# AWSAM5_CS704.net
KiCad netlist of a schematic drawn in Altium Designer
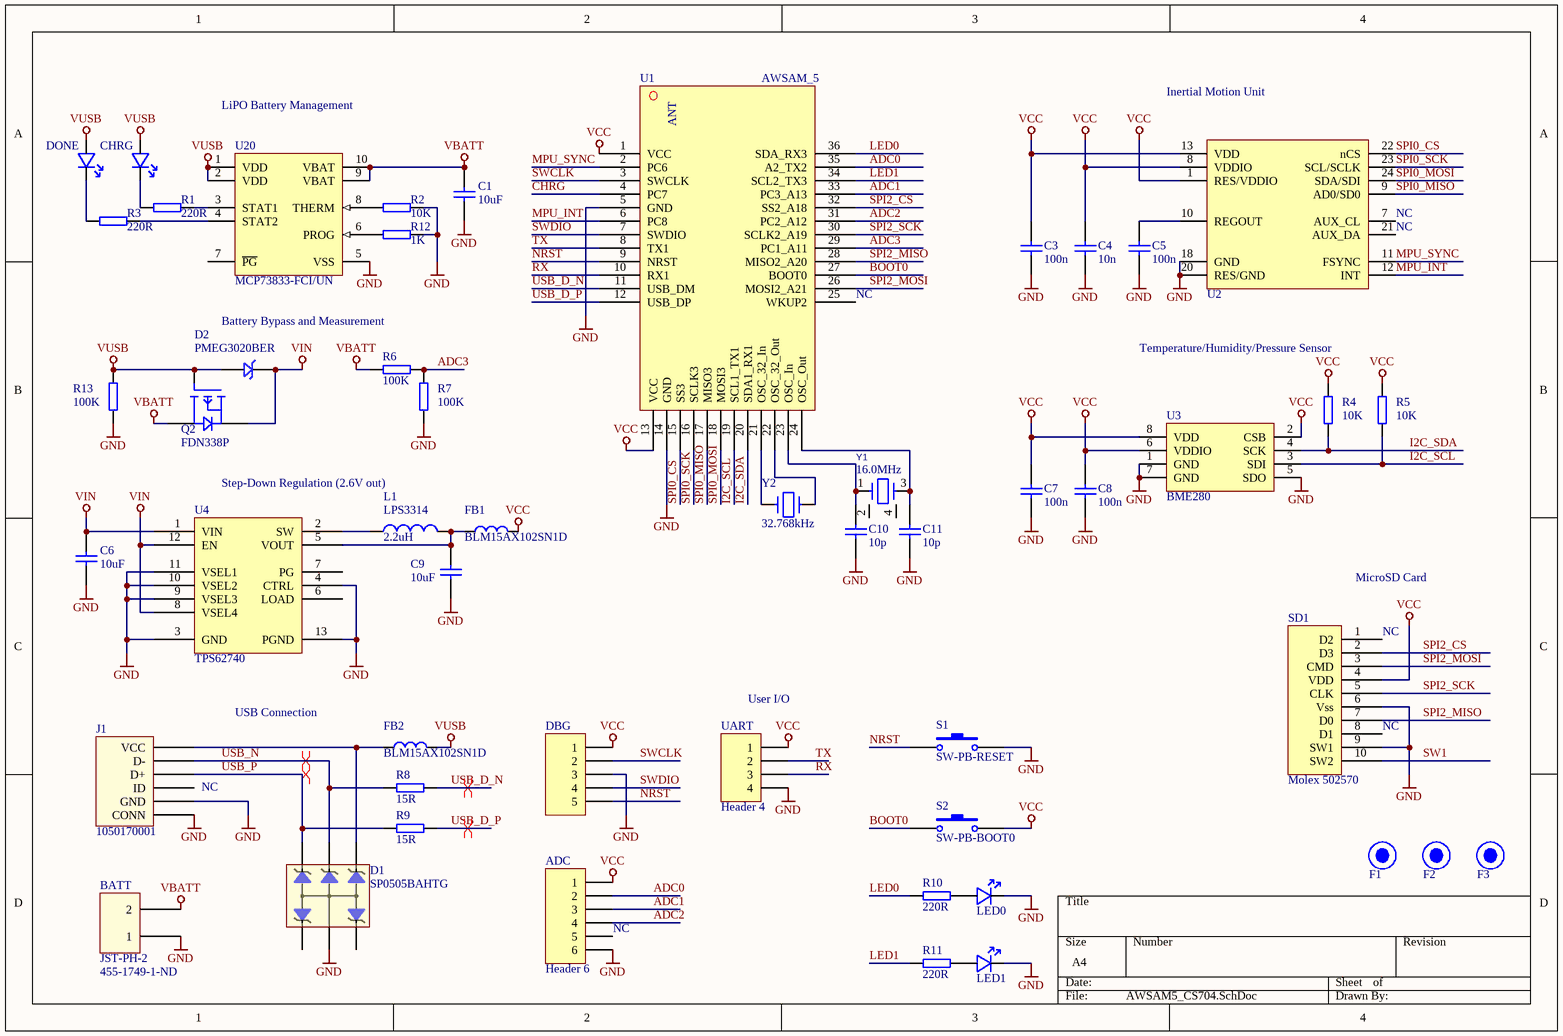
[diagram p0: AWSAM5_CS704.SchDoc]

(export (version "E")
  (design (tool "Eeschema 10.0.6"))
  (components
    (comp (ref "ADC")
      (value "Header 6")
      (footprint "HDR1X6")
      (description "Header, 6-Pin")
      (fields (field (name "PUBLISHER") "Altium Limited"))
      (libsource (lib "Miscellaneous Connectors") (part "Header 6"))
    )
    (comp (ref "BATT")
      (value "JST-PH-2")
      (footprint "JST-PH-2POS")
      (description "CONN SM JST PH 2-POS")
      (fields (field (name "SUPPLIER PART NUMBER 1") "455-1749-1-ND"))
      (libsource (lib "electronpowered") (part "S2B-PH-SM4-TB"))
    )
    (comp (ref "C1")
      (value "10uF")
      (footprint "CAP0603")
      (description "CAP SM 0603 X5R 10uF")
      (fields (field (name "PART NUMBER") "CAP-SM-0603-X5R-10uF") (field (name "MANUFACTURER") "GENERIC"))
      (libsource (lib "electronpowered") (part "CAP"))
    )
    (comp (ref "C3")
      (value "100n")
      (footprint "CAP0402")
      (description "CAP SM 0402 X7R 100NF")
      (fields (field (name "PART NUMBER") "CAP-SM-0402-X7R-100NF") (field (name "MANUFACTURER") "GENERIC"))
      (libsource (lib "electronpowered") (part "CAP"))
    )
    (comp (ref "C4")
      (value "10n")
      (footprint "CAP0402")
      (description "CAP SM 0402 X7R 10NF")
      (fields (field (name "PART NUMBER") "CAP-SM-0402-X7R-10NF") (field (name "MANUFACTURER") "GENERIC"))
      (libsource (lib "electronpowered") (part "CAP"))
    )
    (comp (ref "C5")
      (value "100n")
      (footprint "CAP0402")
      (description "CAP SM 0402 X7R 100NF")
      (fields (field (name "PART NUMBER") "CAP-SM-0402-X7R-100NF") (field (name "MANUFACTURER") "GENERIC"))
      (libsource (lib "electronpowered") (part "CAP"))
    )
    (comp (ref "C6")
      (value "10uF")
      (footprint "CAP0603")
      (description "CAP SM 0603 X5R 10uF")
      (fields (field (name "PART NUMBER") "CAP-SM-0603-X5R-10uF") (field (name "MANUFACTURER") "GENERIC"))
      (libsource (lib "electronpowered") (part "CAP"))
    )
    (comp (ref "C7")
      (value "100n")
      (footprint "CAP0402")
      (description "CAP SM 0402 X7R 100NF")
      (fields (field (name "PART NUMBER") "CAP-SM-0402-X7R-100NF") (field (name "MANUFACTURER") "GENERIC"))
      (libsource (lib "electronpowered") (part "CAP"))
    )
    (comp (ref "C8")
      (value "100n")
      (footprint "CAP0402")
      (description "CAP SM 0402 X7R 100NF")
      (fields (field (name "PART NUMBER") "CAP-SM-0402-X7R-100NF") (field (name "MANUFACTURER") "GENERIC"))
      (libsource (lib "electronpowered") (part "CAP"))
    )
    (comp (ref "C9")
      (value "10uF")
      (footprint "CAP0603")
      (description "CAP SM 0603 X5R 10uF")
      (fields (field (name "PART NUMBER") "CAP-SM-0603-X5R-10uF") (field (name "MANUFACTURER") "GENERIC"))
      (libsource (lib "electronpowered") (part "CAP"))
    )
    (comp (ref "C10")
      (value "10p")
      (footprint "CAP0402")
      (description "CAP SM 0402 NP0 10PF")
      (fields (field (name "PART NUMBER") "CAP-SM-0402-NP0-10PF") (field (name "MANUFACTURER") "GENERIC"))
      (libsource (lib "electronpowered") (part "CAP"))
    )
    (comp (ref "C11")
      (value "10p")
      (footprint "CAP0402")
      (description "CAP SM 0402 NP0 10PF")
      (fields (field (name "PART NUMBER") "CAP-SM-0402-NP0-10PF") (field (name "MANUFACTURER") "GENERIC"))
      (libsource (lib "electronpowered") (part "CAP"))
    )
    (comp (ref "CHRG")
      (value "LED")
      (footprint "LED0603P")
      (description "LED 0603 RED")
      (fields (field (name "PART NUMBER") "LED-0603-RED") (field (name "MANUFACTURER") "GENERIC"))
      (libsource (lib "electronpowered") (part "LED"))
    )
    (comp (ref "D1")
      (value "SP0505BAHTG")
      (footprint "SOT26A-6L")
      (description "IC DIODE TRANS VOLT SUPPR 5 PACKAGE")
      (fields (field (name "MANUFACTURER") "Little Fuse"))
      (libsource (lib "electronpowered") (part "SP0505BAHTG"))
    )
    (comp (ref "D2")
      (value "DIODE-SCHOTTKY")
      (footprint "SODFL350X110-2N")
      (description "DIODE  SCHOTTKY 1A 40V")
      (fields (field (name "PART NUMBER") "PMEG3020BER") (field (name "MANUFACTURER") "Panasonic"))
      (libsource (lib "electronpowered") (part "DIODE-SCHOTTKY"))
    )
    (comp (ref "DBG")
      (value "~")
      (footprint "HDR1X5")
      (description "Header, 5-Pin")
      (fields (field (name "PUBLISHER") "Altium Limited"))
      (libsource (lib "Miscellaneous Connectors") (part "Header 5"))
    )
    (comp (ref "DONE")
      (value "LED")
      (footprint "LED0603P")
      (description "LED 0603 RED")
      (fields (field (name "PART NUMBER") "LED-0603-RED") (field (name "MANUFACTURER") "GENERIC"))
      (libsource (lib "electronpowered") (part "LED"))
    )
    (comp (ref "F1")
      (value "FIDUCIAL")
      (footprint "FIDUCIAL-1MM")
      (description "FIDUCIAL 1MM CENTER")
      (fields (field (name "PART NUMBER") "FIDUCIAL-1MM"))
      (libsource (lib "electronpowered") (part "FIDUCIAL"))
    )
    (comp (ref "F2")
      (value "FIDUCIAL")
      (footprint "FIDUCIAL-1MM")
      (description "FIDUCIAL 1MM CENTER")
      (fields (field (name "PART NUMBER") "FIDUCIAL-1MM"))
      (libsource (lib "electronpowered") (part "FIDUCIAL"))
    )
    (comp (ref "F3")
      (value "FIDUCIAL")
      (footprint "FIDUCIAL-1MM")
      (description "FIDUCIAL 1MM CENTER")
      (fields (field (name "PART NUMBER") "FIDUCIAL-1MM"))
      (libsource (lib "electronpowered") (part "FIDUCIAL"))
    )
    (comp (ref "FB1")
      (value "IND")
      (footprint "IND0402")
      (description "FERRITE BEAD 350mA 0402")
      (fields (field (name "PART NUMBER") "BLM15AX102SN1D") (field (name "MANUFACTURER") "Murata"))
      (libsource (lib "electronpowered") (part "IND"))
    )
    (comp (ref "FB2")
      (value "IND")
      (footprint "IND0402")
      (description "FERRITE BEAD 350mA 0402")
      (fields (field (name "PART NUMBER") "BLM15AX102SN1D") (field (name "MANUFACTURER") "Murata"))
      (libsource (lib "electronpowered") (part "IND"))
    )
    (comp (ref "J1")
      (value "1050170001")
      (footprint "1050170001")
      (description "CONN RCPT MICRO USB R/A SMD")
      (fields (field (name "MANUFACTURER") "MOLEX"))
      (libsource (lib "electronpowered") (part "1050170001"))
    )
    (comp (ref "L1")
      (value "LPS3314")
      (footprint "CoilCraft- LPS3314")
      (description "Inductor")
      (fields (field (name "ALTIUM_VALUE") "2.2uH") (field (name "PUBLISHER") "Altium Limited"))
      (libsource (lib "Miscellaneous Devices") (part "Inductor"))
    )
    (comp (ref "LED0")
      (value "LED")
      (footprint "LED0603P")
      (description "LED 0603 RED")
      (fields (field (name "PART NUMBER") "LED-0603-RED") (field (name "MANUFACTURER") "GENERIC"))
      (libsource (lib "electronpowered") (part "LED"))
    )
    (comp (ref "LED1")
      (value "LED")
      (footprint "LED0603P")
      (description "LED 0603 RED")
      (fields (field (name "PART NUMBER") "LED-0603-RED") (field (name "MANUFACTURER") "GENERIC"))
      (libsource (lib "electronpowered") (part "LED"))
    )
    (comp (ref "Q2")
      (value "FET-PCH-DIODE")
      (footprint "SOT23-3")
      (description "MOSFET P-CH 20V 115MA SOT23-3")
      (fields (field (name "PART NUMBER") "FDN338P") (field (name "MANUFACTURER") "Fairchild"))
      (libsource (lib "electronpowered") (part "FET-PCH-DIODE"))
    )
    (comp (ref "R1")
      (value "220R")
      (footprint "SMT0402")
      (description "RES SM 0603 220R")
      (fields (field (name "Comment") "Resistor"))
      (libsource (lib "electronpowered") (part "RES-SM-0603-220R"))
    )
    (comp (ref "R2")
      (value "10K")
      (footprint "SMT0402")
      (description "RES SM 0402 10K")
      (fields (field (name "PART NUMBER") "RES-SM-0402-10K") (field (name "MANUFACTURER") "GENERIC"))
      (libsource (lib "electronpowered") (part "RES"))
    )
    (comp (ref "R3")
      (value "220R")
      (footprint "SMT0402")
      (description "RES SM 0603 220R")
      (fields (field (name "Comment") "Resistor"))
      (libsource (lib "electronpowered") (part "RES-SM-0603-220R"))
    )
    (comp (ref "R4")
      (value "10K")
      (footprint "SMT0402")
      (description "RES SM 0402 10K")
      (fields (field (name "PART NUMBER") "RES-SM-0402-10K") (field (name "MANUFACTURER") "GENERIC"))
      (libsource (lib "electronpowered") (part "RES"))
    )
    (comp (ref "R5")
      (value "10K")
      (footprint "SMT0402")
      (description "RES SM 0402 10K")
      (fields (field (name "PART NUMBER") "RES-SM-0402-10K") (field (name "MANUFACTURER") "GENERIC"))
      (libsource (lib "electronpowered") (part "RES"))
    )
    (comp (ref "R6")
      (value "100K")
      (footprint "SMT0402")
      (description "RES SM 0402 100K")
      (fields (field (name "PART NUMBER") "RES-SM-0402-100K") (field (name "MANUFACTURER") "GENERIC"))
      (libsource (lib "electronpowered") (part "RES"))
    )
    (comp (ref "R7")
      (value "100K")
      (footprint "SMT0402")
      (description "RES SM 0402 100K")
      (fields (field (name "PART NUMBER") "RES-SM-0402-100K") (field (name "MANUFACTURER") "GENERIC"))
      (libsource (lib "electronpowered") (part "RES"))
    )
    (comp (ref "R8")
      (value "15R")
      (footprint "SMT0402")
      (description "RES SM 0603 22K")
      (libsource (lib "electronpowered") (part "RES-SM-0603-22K"))
    )
    (comp (ref "R9")
      (value "15R")
      (footprint "SMT0402")
      (description "RES SM 0603 22K")
      (fields (field (name "Comment") "Resistor"))
      (libsource (lib "electronpowered") (part "RES-SM-0603-22K"))
    )
    (comp (ref "R10")
      (value "220R")
      (footprint "SMT0402")
      (description "RES SM 0603 220R")
      (fields (field (name "Comment") "Resistor"))
      (libsource (lib "electronpowered") (part "RES-SM-0603-220R"))
    )
    (comp (ref "R11")
      (value "220R")
      (footprint "SMT0402")
      (description "RES SM 0603 220R")
      (fields (field (name "Comment") "Resistor"))
      (libsource (lib "electronpowered") (part "RES-SM-0603-220R"))
    )
    (comp (ref "R12")
      (value "1K")
      (footprint "SMT0402")
      (description "RES SM 0402 1K")
      (fields (field (name "PART NUMBER") "RES-SM-0402-1K") (field (name "MANUFACTURER") "GENERIC"))
      (libsource (lib "electronpowered") (part "RES"))
    )
    (comp (ref "R13")
      (value "100K")
      (footprint "RES0402")
      (description "RES SM 0402 100K")
      (fields (field (name "PART NUMBER") "RES-SM-0402-100K") (field (name "MANUFACTURER") "GENERIC"))
      (libsource (lib "") (part "RES_1"))
    )
    (comp (ref "S1")
      (value "SW-PB-RESET")
      (footprint "MC32882 Switch")
      (description "Switch")
      (fields (field (name "PUBLISHER") "Altium Limited"))
      (libsource (lib "Miscellaneous Devices") (part "SW-PB"))
    )
    (comp (ref "S2")
      (value "SW-PB-BOOT0")
      (footprint "MC32882 Switch")
      (description "Switch")
      (fields (field (name "PUBLISHER") "Altium Limited"))
      (libsource (lib "Miscellaneous Devices") (part "SW-PB"))
    )
    (comp (ref "SD1")
      (value "Molex 502570")
      (footprint "micro SD")
      (description "CONN SM MICROSD")
      (libsource (lib "AWSAM_5") (part "MOLEX-502570"))
    )
    (comp (ref "U1") (value "AWSAM_5") (footprint "AWSAM_5") (libsource (lib "AWSAM_5") (part "AWSAM_5")))
    (comp (ref "U2")
      (value "MPU-9250")
      (footprint "QFN40P300X300X105_HS-25L")
      (description "IC 9DOF IMU")
      (fields (field (name "MANUFACTURER") "InvenSense"))
      (libsource (lib "electronpowered") (part "MPU-9250"))
    )
    (comp (ref "U3")
      (value "BME280")
      (footprint "BME280")
      (description "IC SENSOR PRESS/HUMID/TEMP")
      (fields (field (name "MANUFACTURER") "Bosch"))
      (libsource (lib "electronpowered") (part "BME280"))
    )
    (comp (ref "U4")
      (value "TPS62740")
      (footprint "TPS62740_12Pin")
      (description "IC REG BUCK")
      (fields (field (name "MANUFACTURER") "Texas Instruments"))
      (libsource (lib "electronpowered") (part "TPS62740"))
    )
    (comp (ref "U20")
      (value "MCP73833-FCI/UN")
      (footprint "MSOP-UN10_N")
      (fields (field (name "PUBLISHER") "Altium Limited"))
      (libsource (lib "Microchip Power Mgt Battery Management") (part "MCP73833-FCI/UN"))
    )
    (comp (ref "UART")
      (value "Header 4")
      (footprint "HDR1X4")
      (description "Header, 4-Pin")
      (fields (field (name "PUBLISHER") "Altium Limited"))
      (libsource (lib "Miscellaneous Connectors") (part "Header 4"))
    )
    (comp (ref "Y1")
      (value "16.0MHz")
      (footprint "AP7-00061")
      (description "16MHz uXtal, 3.2 x 2.5 mm SMD, CL=9pF, 15PPM, ESR=80ohm(Max.")
      (fields (field (name "TOLERANCE") "15ppm") (field (name "MANUFACTURER") "Epson Toyocom"))
      (libsource (lib "AltiumDbLib") (part "TSX-3225"))
    )
    (comp (ref "Y2")
      (value "CM315-32.768KEZF-UT")
      (footprint "SMD Crystal 32kHz")
      (description "CRYSTAL 32.768KHZ 12.5PF SMD")
      (fields (field (name "MANUFACTURER") "Citizen Finetech Miyota") (field (name "FREQUENCY") "32.768kHz"))
      (libsource (lib "AWSAM_5") (part "CM315-32.768KEZF-UT"))
    )
  )
  (nets
    (net (code "1") (name "/ADC0") (class "Default")
      (node (ref "ADC") (pin "2") (pinfunction "2_2") (pintype "passive"))
      (node (ref "U1") (pin "35") (pinfunction "A2_TX2_35") (pintype "passive"))
    )
    (net (code "2") (name "/ADC1") (class "Default")
      (node (ref "ADC") (pin "3") (pinfunction "3_3") (pintype "passive"))
      (node (ref "U1") (pin "33") (pinfunction "PC3_A13_33") (pintype "passive"))
    )
    (net (code "3") (name "/ADC2") (class "Default")
      (node (ref "ADC") (pin "4") (pinfunction "4_4") (pintype "passive"))
      (node (ref "U1") (pin "31") (pinfunction "PC2_A12_31") (pintype "passive"))
    )
    (net (code "4") (name "/ADC3") (class "Default")
      (node (ref "R6") (pin "1") (pinfunction "1_1") (pintype "passive"))
      (node (ref "R7") (pin "2") (pinfunction "2_2") (pintype "passive"))
      (node (ref "U1") (pin "29") (pinfunction "PC1_A11_29") (pintype "passive"))
    )
    (net (code "5") (name "/BOOT0") (class "Default")
      (node (ref "S2") (pin "1") (pinfunction "1_1") (pintype "passive"))
      (node (ref "U1") (pin "27") (pinfunction "BOOT0_27") (pintype "passive"))
    )
    (net (code "6") (name "/CHRG") (class "Default")
      (node (ref "U1") (pin "4") (pinfunction "PC7_4") (pintype "passive"))
    )
    (net (code "7") (name "/I2C_SCL") (class "Default")
      (node (ref "R5") (pin "1") (pinfunction "1_1") (pintype "passive"))
      (node (ref "U1") (pin "19") (pinfunction "SCL1_TX1_19") (pintype "passive"))
      (node (ref "U3") (pin "3") (pinfunction "SDI_3") (pintype "passive"))
    )
    (net (code "8") (name "/I2C_SDA") (class "Default")
      (node (ref "R4") (pin "1") (pinfunction "1_1") (pintype "passive"))
      (node (ref "U1") (pin "20") (pinfunction "SDA1_RX1_20") (pintype "passive"))
      (node (ref "U3") (pin "4") (pinfunction "SCK_4") (pintype "passive"))
    )
    (net (code "9") (name "/LED0") (class "Default")
      (node (ref "R10") (pin "2") (pinfunction "2_2") (pintype "passive"))
      (node (ref "U1") (pin "36") (pinfunction "SDA_RX3_36") (pintype "passive"))
    )
    (net (code "10") (name "/LED1") (class "Default")
      (node (ref "R11") (pin "2") (pinfunction "2_2") (pintype "passive"))
      (node (ref "U1") (pin "34") (pinfunction "SCL2_TX3_34") (pintype "passive"))
    )
    (net (code "11") (name "/MPU_INT") (class "Default")
      (node (ref "U1") (pin "6") (pinfunction "PC8_6") (pintype "passive"))
      (node (ref "U2") (pin "12") (pinfunction "INT_12") (pintype "passive"))
    )
    (net (code "12") (name "/MPU_SYNC") (class "Default")
      (node (ref "U1") (pin "2") (pinfunction "PC6_2") (pintype "passive"))
      (node (ref "U2") (pin "11") (pinfunction "FSYNC_11") (pintype "passive"))
    )
    (net (code "13") (name "/NRST") (class "Default")
      (node (ref "DBG") (pin "5") (pinfunction "5_5") (pintype "passive"))
      (node (ref "S1") (pin "1") (pinfunction "1_1") (pintype "passive"))
      (node (ref "U1") (pin "9") (pinfunction "NRST_9") (pintype "passive"))
    )
    (net (code "14") (name "/RX") (class "Default")
      (node (ref "U1") (pin "10") (pinfunction "RX1_10") (pintype "passive"))
      (node (ref "UART") (pin "3") (pinfunction "3_3") (pintype "passive"))
    )
    (net (code "15") (name "/SPI0_CS") (class "Default")
      (node (ref "U1") (pin "15") (pinfunction "SS3_15") (pintype "passive"))
      (node (ref "U2") (pin "22") (pinfunction "nCS_22") (pintype "passive"))
    )
    (net (code "16") (name "/SPI0_MISO") (class "Default")
      (node (ref "U1") (pin "17") (pinfunction "MISO3_17") (pintype "passive"))
      (node (ref "U2") (pin "9") (pinfunction "AD0/SD0_9") (pintype "passive"))
    )
    (net (code "17") (name "/SPI0_MOSI") (class "Default")
      (node (ref "U1") (pin "18") (pinfunction "MOSI3_18") (pintype "passive"))
      (node (ref "U2") (pin "24") (pinfunction "SDA/SDI_24") (pintype "passive"))
    )
    (net (code "18") (name "/SPI0_SCK") (class "Default")
      (node (ref "U1") (pin "16") (pinfunction "SCLK3_16") (pintype "passive"))
      (node (ref "U2") (pin "23") (pinfunction "SCL/SCLK_23") (pintype "passive"))
    )
    (net (code "19") (name "/SPI2_CS") (class "Default")
      (node (ref "SD1") (pin "2") (pinfunction "D3_2") (pintype "passive"))
      (node (ref "U1") (pin "32") (pinfunction "SS2_A18_32") (pintype "passive"))
    )
    (net (code "20") (name "/SPI2_MISO") (class "Default")
      (node (ref "SD1") (pin "7") (pinfunction "D0_7") (pintype "passive"))
      (node (ref "U1") (pin "28") (pinfunction "MISO2_A20_28") (pintype "passive"))
    )
    (net (code "21") (name "/SPI2_MOSI") (class "Default")
      (node (ref "SD1") (pin "3") (pinfunction "CMD_3") (pintype "passive"))
      (node (ref "U1") (pin "26") (pinfunction "MOSI2_A21_26") (pintype "passive"))
    )
    (net (code "22") (name "/SPI2_SCK") (class "Default")
      (node (ref "SD1") (pin "5") (pinfunction "CLK_5") (pintype "passive"))
      (node (ref "U1") (pin "30") (pinfunction "SCLK2_A19_30") (pintype "passive"))
    )
    (net (code "23") (name "/SW1") (class "Default")
      (node (ref "SD1") (pin "10") (pinfunction "SW2_10") (pintype "passive"))
    )
    (net (code "24") (name "/SWCLK") (class "Default")
      (node (ref "DBG") (pin "2") (pinfunction "2_2") (pintype "passive"))
      (node (ref "U1") (pin "3") (pinfunction "SWCLK_3") (pintype "passive"))
    )
    (net (code "25") (name "/SWDIO") (class "Default")
      (node (ref "DBG") (pin "4") (pinfunction "4_4") (pintype "passive"))
      (node (ref "U1") (pin "7") (pinfunction "SWDIO_7") (pintype "passive"))
    )
    (net (code "26") (name "/TX") (class "Default")
      (node (ref "U1") (pin "8") (pinfunction "TX1_8") (pintype "passive"))
      (node (ref "UART") (pin "2") (pinfunction "2_2") (pintype "passive"))
    )
    (net (code "27") (name "/USB_D_N") (class "Default")
      (node (ref "R8") (pin "1") (pinfunction "1_1") (pintype "passive"))
      (node (ref "U1") (pin "11") (pinfunction "USB_DM_11") (pintype "passive"))
    )
    (net (code "28") (name "/USB_D_P") (class "Default")
      (node (ref "R9") (pin "1") (pinfunction "1_1") (pintype "passive"))
      (node (ref "U1") (pin "12") (pinfunction "USB_DP_12") (pintype "passive"))
    )
    (net (code "29") (name "/USB_N") (class "Default")
      (node (ref "D1") (pin "5") (pinfunction "5_5") (pintype "passive"))
      (node (ref "J1") (pin "2") (pinfunction "D-_2") (pintype "passive"))
      (node (ref "R8") (pin "2") (pinfunction "2_2") (pintype "passive"))
    )
    (net (code "30") (name "/USB_P") (class "Default")
      (node (ref "D1") (pin "6") (pinfunction "6_6") (pintype "passive"))
      (node (ref "J1") (pin "3") (pinfunction "D+_3") (pintype "passive"))
      (node (ref "R9") (pin "2") (pinfunction "2_2") (pintype "passive"))
    )
    (net (code "31") (name "GND") (class "Default")
      (node (ref "ADC") (pin "6") (pinfunction "6_6") (pintype "passive"))
      (node (ref "BATT") (pin "1") (pinfunction "1_1") (pintype "passive"))
      (node (ref "C1") (pin "1") (pinfunction "1_1") (pintype "passive"))
      (node (ref "C10") (pin "1") (pinfunction "1_1") (pintype "passive"))
      (node (ref "C11") (pin "1") (pinfunction "1_1") (pintype "passive"))
      (node (ref "C3") (pin "1") (pinfunction "1_1") (pintype "passive"))
      (node (ref "C4") (pin "1") (pinfunction "1_1") (pintype "passive"))
      (node (ref "C5") (pin "1") (pinfunction "1_1") (pintype "passive"))
      (node (ref "C6") (pin "1") (pinfunction "1_1") (pintype "passive"))
      (node (ref "C7") (pin "1") (pinfunction "1_1") (pintype "passive"))
      (node (ref "C8") (pin "1") (pinfunction "1_1") (pintype "passive"))
      (node (ref "C9") (pin "1") (pinfunction "1_1") (pintype "passive"))
      (node (ref "D1") (pin "2") (pinfunction "2_2") (pintype "passive"))
      (node (ref "DBG") (pin "3") (pinfunction "3_3") (pintype "passive"))
      (node (ref "J1") (pin "0") (pinfunction "CONN_0") (pintype "passive"))
      (node (ref "J1") (pin "5") (pinfunction "GND_5") (pintype "passive"))
      (node (ref "LED0") (pin "2") (pinfunction "2_2") (pintype "passive"))
      (node (ref "LED1") (pin "2") (pinfunction "2_2") (pintype "passive"))
      (node (ref "R12") (pin "2") (pinfunction "2_2") (pintype "passive"))
      (node (ref "R13") (pin "1") (pinfunction "1_1") (pintype "passive"))
      (node (ref "R2") (pin "2") (pinfunction "2_2") (pintype "passive"))
      (node (ref "R7") (pin "1") (pinfunction "1_1") (pintype "passive"))
      (node (ref "S1") (pin "2") (pinfunction "2_2") (pintype "passive"))
      (node (ref "SD1") (pin "6") (pinfunction "Vss_6") (pintype "passive"))
      (node (ref "SD1") (pin "9") (pinfunction "SW1_9") (pintype "passive"))
      (node (ref "U1") (pin "14") (pinfunction "GND_14") (pintype "passive"))
      (node (ref "U1") (pin "5") (pinfunction "GND_5") (pintype "passive"))
      (node (ref "U2") (pin "18") (pinfunction "GND_18") (pintype "passive"))
      (node (ref "U2") (pin "20") (pinfunction "RES/GND_20") (pintype "passive"))
      (node (ref "U20") (pin "5") (pinfunction "VSS_5") (pintype "power_in"))
      (node (ref "U3") (pin "1") (pinfunction "GND_1") (pintype "passive"))
      (node (ref "U3") (pin "5") (pinfunction "SDO_5") (pintype "passive"))
      (node (ref "U3") (pin "7") (pinfunction "GND_7") (pintype "passive"))
      (node (ref "U4") (pin "10") (pinfunction "VSEL2_10") (pintype "passive"))
      (node (ref "U4") (pin "11") (pinfunction "VSEL1_11") (pintype "passive"))
      (node (ref "U4") (pin "13") (pinfunction "PGND_13") (pintype "passive"))
      (node (ref "U4") (pin "3") (pinfunction "GND_3") (pintype "passive"))
      (node (ref "U4") (pin "4") (pinfunction "CTRL_4") (pintype "passive"))
      (node (ref "U4") (pin "9") (pinfunction "VSEL3_9") (pintype "passive"))
      (node (ref "UART") (pin "4") (pinfunction "4_4") (pintype "passive"))
    )
    (net (code "32") (name "Net-(CHRG-Pad2)") (class "Default")
      (node (ref "CHRG") (pin "2") (pinfunction "2_2") (pintype "passive"))
      (node (ref "R1") (pin "2") (pinfunction "2_2") (pintype "passive"))
    )
    (net (code "33") (name "Net-(DONE-Pad2)") (class "Default")
      (node (ref "DONE") (pin "2") (pinfunction "2_2") (pintype "passive"))
      (node (ref "R3") (pin "2") (pinfunction "2_2") (pintype "passive"))
    )
    (net (code "34") (name "Net-(J1-VCC)") (class "Default")
      (node (ref "D1") (pin "4") (pinfunction "4_4") (pintype "passive"))
      (node (ref "FB2") (pin "1") (pinfunction "1_1") (pintype "passive"))
      (node (ref "J1") (pin "1") (pinfunction "VCC_1") (pintype "passive"))
    )
    (net (code "35") (name "Net-(LED0-Pad1)") (class "Default")
      (node (ref "LED0") (pin "1") (pinfunction "1_1") (pintype "passive"))
      (node (ref "R10") (pin "1") (pinfunction "1_1") (pintype "passive"))
    )
    (net (code "36") (name "Net-(LED1-Pad1)") (class "Default")
      (node (ref "LED1") (pin "1") (pinfunction "1_1") (pintype "passive"))
      (node (ref "R11") (pin "1") (pinfunction "1_1") (pintype "passive"))
    )
    (net (code "37") (name "Net-(U1-OSC_32_In)") (class "Default")
      (node (ref "U1") (pin "21") (pinfunction "OSC_32_In_21") (pintype "passive"))
      (node (ref "Y2") (pin "1") (pinfunction "IN_1") (pintype "passive"))
    )
    (net (code "38") (name "Net-(U1-OSC_32_Out)") (class "Default")
      (node (ref "U1") (pin "22") (pinfunction "OSC_32_Out_22") (pintype "passive"))
      (node (ref "Y2") (pin "2") (pinfunction "OUT_2") (pintype "passive"))
    )
    (net (code "39") (name "Net-(U1-OSC_In)") (class "Default")
      (node (ref "C10") (pin "2") (pinfunction "2_2") (pintype "passive"))
      (node (ref "U1") (pin "23") (pinfunction "OSC_In_23") (pintype "passive"))
      (node (ref "Y1") (pin "1") (pinfunction "IN_1") (pintype "passive"))
    )
    (net (code "40") (name "Net-(U1-OSC_Out)") (class "Default")
      (node (ref "C11") (pin "2") (pinfunction "2_2") (pintype "passive"))
      (node (ref "U1") (pin "24") (pinfunction "OSC_Out_24") (pintype "passive"))
      (node (ref "Y1") (pin "3") (pinfunction "OUT_3") (pintype "passive"))
    )
    (net (code "41") (name "Net-(U2-REGOUT)") (class "Default")
      (node (ref "C5") (pin "2") (pinfunction "2_2") (pintype "passive"))
      (node (ref "U2") (pin "10") (pinfunction "REGOUT_10") (pintype "passive"))
    )
    (net (code "42") (name "Net-(U4-SW)") (class "Default")
      (node (ref "L1") (pin "1") (pinfunction "1_1") (pintype "passive"))
      (node (ref "U4") (pin "2") (pinfunction "SW_2") (pintype "passive"))
    )
    (net (code "43") (name "Net-(U4-VOUT)") (class "Default")
      (node (ref "C9") (pin "2") (pinfunction "2_2") (pintype "passive"))
      (node (ref "FB1") (pin "1") (pinfunction "1_1") (pintype "passive"))
      (node (ref "L1") (pin "2") (pinfunction "2_2") (pintype "passive"))
      (node (ref "U4") (pin "5") (pinfunction "VOUT_5") (pintype "passive"))
    )
    (net (code "44") (name "Net-(U20-PROG)") (class "Default")
      (node (ref "R12") (pin "1") (pinfunction "1_1") (pintype "passive"))
      (node (ref "U20") (pin "6") (pinfunction "PROG_6") (pintype "input"))
    )
    (net (code "45") (name "Net-(U20-STAT1)") (class "Default")
      (node (ref "R1") (pin "1") (pinfunction "1_1") (pintype "passive"))
      (node (ref "U20") (pin "3") (pinfunction "STAT1_3") (pintype "open_collector"))
    )
    (net (code "46") (name "Net-(U20-STAT2)") (class "Default")
      (node (ref "R3") (pin "1") (pinfunction "1_1") (pintype "passive"))
      (node (ref "U20") (pin "4") (pinfunction "STAT2_4") (pintype "open_collector"))
    )
    (net (code "47") (name "Net-(U20-THERM)") (class "Default")
      (node (ref "R2") (pin "1") (pinfunction "1_1") (pintype "passive"))
      (node (ref "U20") (pin "8") (pinfunction "THERM_8") (pintype "input"))
    )
    (net (code "48") (name "VBATT") (class "Default")
      (node (ref "BATT") (pin "2") (pinfunction "2_2") (pintype "passive"))
      (node (ref "C1") (pin "2") (pinfunction "2_2") (pintype "passive"))
      (node (ref "Q2") (pin "3") (pinfunction "3_3") (pintype "passive"))
      (node (ref "R6") (pin "2") (pinfunction "2_2") (pintype "passive"))
      (node (ref "U20") (pin "10") (pinfunction "VBAT_10") (pintype "power_in"))
      (node (ref "U20") (pin "9") (pinfunction "VBAT_9") (pintype "power_in"))
    )
    (net (code "49") (name "VCC") (class "Default")
      (node (ref "ADC") (pin "1") (pinfunction "1_1") (pintype "passive"))
      (node (ref "C3") (pin "2") (pinfunction "2_2") (pintype "passive"))
      (node (ref "C4") (pin "2") (pinfunction "2_2") (pintype "passive"))
      (node (ref "C7") (pin "2") (pinfunction "2_2") (pintype "passive"))
      (node (ref "C8") (pin "2") (pinfunction "2_2") (pintype "passive"))
      (node (ref "DBG") (pin "1") (pinfunction "1_1") (pintype "passive"))
      (node (ref "FB1") (pin "2") (pinfunction "2_2") (pintype "passive"))
      (node (ref "R4") (pin "2") (pinfunction "2_2") (pintype "passive"))
      (node (ref "R5") (pin "2") (pinfunction "2_2") (pintype "passive"))
      (node (ref "S2") (pin "2") (pinfunction "2_2") (pintype "passive"))
      (node (ref "SD1") (pin "4") (pinfunction "VDD_4") (pintype "passive"))
      (node (ref "U1") (pin "1") (pinfunction "VCC_1") (pintype "passive"))
      (node (ref "U1") (pin "13") (pinfunction "VCC_13") (pintype "passive"))
      (node (ref "U2") (pin "1") (pinfunction "RES/VDDIO_1") (pintype "passive"))
      (node (ref "U2") (pin "13") (pinfunction "VDD_13") (pintype "passive"))
      (node (ref "U2") (pin "8") (pinfunction "VDDIO_8") (pintype "passive"))
      (node (ref "U3") (pin "2") (pinfunction "CSB_2") (pintype "passive"))
      (node (ref "U3") (pin "6") (pinfunction "VDDIO_6") (pintype "passive"))
      (node (ref "U3") (pin "8") (pinfunction "VDD_8") (pintype "passive"))
      (node (ref "UART") (pin "1") (pinfunction "1_1") (pintype "passive"))
    )
    (net (code "50") (name "VIN") (class "Default")
      (node (ref "C6") (pin "2") (pinfunction "2_2") (pintype "passive"))
      (node (ref "D2") (pin "1") (pinfunction "1_1") (pintype "passive"))
      (node (ref "Q2") (pin "2") (pinfunction "2_2") (pintype "passive"))
      (node (ref "U4") (pin "1") (pinfunction "VIN_1") (pintype "passive"))
      (node (ref "U4") (pin "12") (pinfunction "EN_12") (pintype "passive"))
      (node (ref "U4") (pin "8") (pinfunction "VSEL4_8") (pintype "passive"))
    )
    (net (code "51") (name "VUSB") (class "Default")
      (node (ref "CHRG") (pin "1") (pinfunction "1_1") (pintype "passive"))
      (node (ref "D2") (pin "2") (pinfunction "2_2") (pintype "passive"))
      (node (ref "DONE") (pin "1") (pinfunction "1_1") (pintype "passive"))
      (node (ref "FB2") (pin "2") (pinfunction "2_2") (pintype "passive"))
      (node (ref "Q2") (pin "1") (pinfunction "1_1") (pintype "passive"))
      (node (ref "R13") (pin "2") (pinfunction "2_2") (pintype "passive"))
      (node (ref "U20") (pin "1") (pinfunction "VDD_1") (pintype "power_in"))
      (node (ref "U20") (pin "2") (pinfunction "VDD_2") (pintype "power_in"))
    )
    (net (code "52") (name "unconnected-(ADC-Pad5)") (class "Default")
      (node (ref "ADC") (pin "5") (pinfunction "5_5") (pintype "passive"))
    )
    (net (code "53") (name "unconnected-(D1-Pad1)") (class "Default")
      (node (ref "D1") (pin "1") (pinfunction "1_1") (pintype "passive"))
    )
    (net (code "54") (name "unconnected-(D1-Pad3)") (class "Default")
      (node (ref "D1") (pin "3") (pinfunction "3_3") (pintype "passive"))
    )
    (net (code "55") (name "unconnected-(J1-ID-Pad4)") (class "Default")
      (node (ref "J1") (pin "4") (pinfunction "ID_4") (pintype "passive"))
    )
    (net (code "56") (name "unconnected-(SD1-D1-Pad8)") (class "Default")
      (node (ref "SD1") (pin "8") (pinfunction "D1_8") (pintype "passive"))
    )
    (net (code "57") (name "unconnected-(SD1-D2-Pad1)") (class "Default")
      (node (ref "SD1") (pin "1") (pinfunction "D2_1") (pintype "passive"))
    )
    (net (code "58") (name "unconnected-(U1-WKUP2-Pad25)") (class "Default")
      (node (ref "U1") (pin "25") (pinfunction "WKUP2_25") (pintype "passive"))
    )
    (net (code "59") (name "unconnected-(U2-AUX_CL-Pad7)") (class "Default")
      (node (ref "U2") (pin "7") (pinfunction "AUX_CL_7") (pintype "passive"))
    )
    (net (code "60") (name "unconnected-(U2-AUX_DA-Pad21)") (class "Default")
      (node (ref "U2") (pin "21") (pinfunction "AUX_DA_21") (pintype "passive"))
    )
    (net (code "61") (name "unconnected-(U4-LOAD-Pad6)") (class "Default")
      (node (ref "U4") (pin "6") (pinfunction "LOAD_6") (pintype "passive"))
    )
    (net (code "62") (name "unconnected-(U4-PG-Pad7)") (class "Default")
      (node (ref "U4") (pin "7") (pinfunction "PG_7") (pintype "passive"))
    )
    (net (code "63") (name "unconnected-(U20-~{PG}-Pad7)") (class "Default")
      (node (ref "U20") (pin "7") (pinfunction "~{PG}_7") (pintype "open_collector"))
    )
    (net (code "64") (name "unconnected-(Y1-GND-Pad2)") (class "Default")
      (node (ref "Y1") (pin "2") (pinfunction "GND_2") (pintype "passive"))
    )
    (net (code "65") (name "unconnected-(Y1-GND-Pad4)") (class "Default")
      (node (ref "Y1") (pin "4") (pinfunction "GND_4") (pintype "passive"))
    )
  )
)
